# PCBproject.net
KiCad netlist of a schematic drawn in EasyEDA
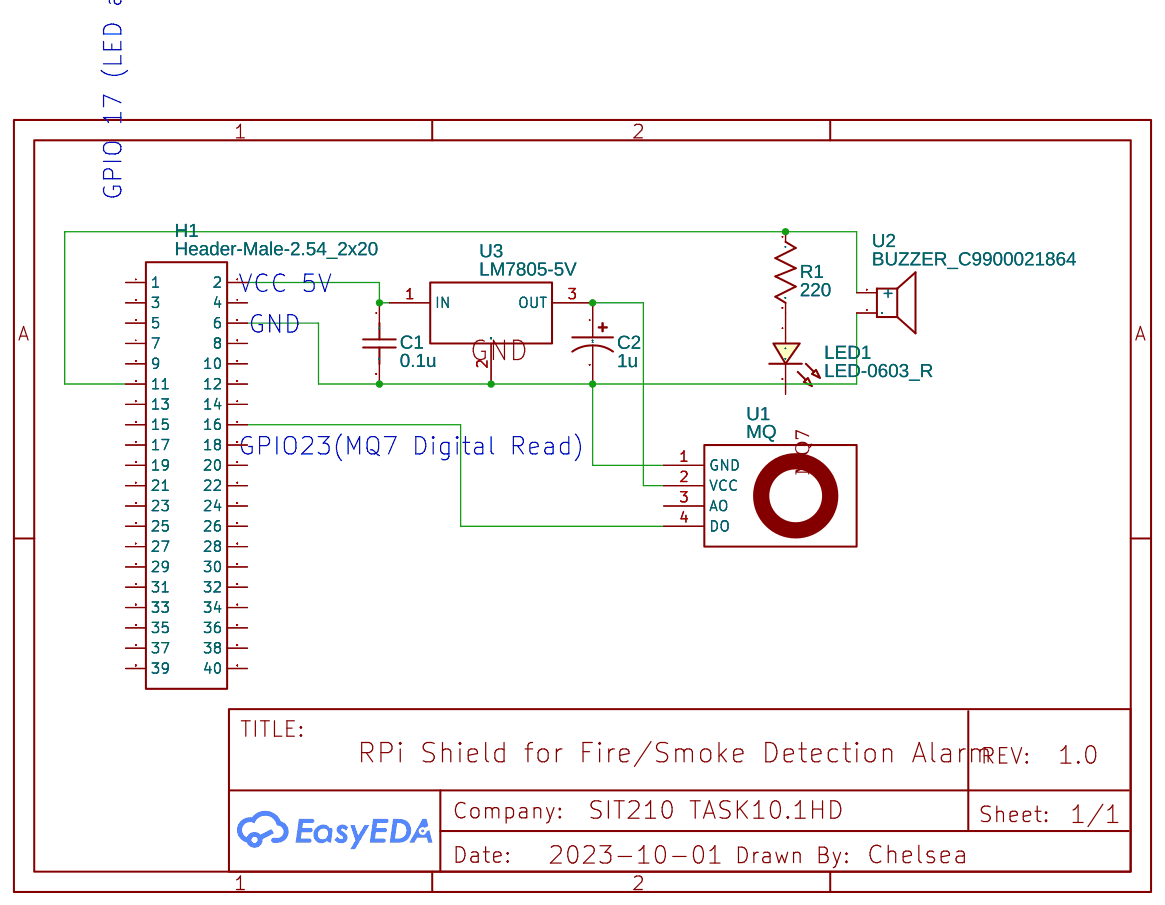
[diagram p0: schematic sheet]

(export (version "E")
  (design (tool "Eeschema 10.0.6"))
  (components
    (comp (ref "C1") (value "0.1u") (libsource (lib "") (part "C_0603_US")))
    (comp (ref "C2") (value "1u") (libsource (lib "") (part "C_Tan_SMD_A_US")))
    (comp (ref "H1")
      (value "Header-Male-2.54_2x20")
      (fields
        (field (name "Manufacturer Part") "2.54mm 2*20P直排针")
        (field (name "Manufacturer") "BOOMELE(博穆精密)")
      )
      (libsource (lib "") (part "Header-Male-2.54_2x20"))
    )
    (comp (ref "LED1")
      (value "LED-0603_R")
      (fields
        (field (name "Manufacturer Part") "19-217/R6C-AL1M2VY/3T")
        (field (name "Manufacturer") "EVERLIGHT(台湾亿光)")
      )
      (libsource (lib "") (part "LED-0603_R"))
    )
    (comp (ref "R1") (value "220") (libsource (lib "") (part "R_0603_US")))
    (comp (ref "U1") (value "MQ") (libsource (lib "") (part "MQ")))
    (comp (ref "U2")
      (value "BUZZER_C9900021864")
      (fields (field (name "Manufacturer Part") "BUZZER"))
      (libsource (lib "") (part "BUZZER_C9900021864"))
    )
    (comp (ref "U3") (value "LM7805-5V") (libsource (lib "") (part "LM7805-5V")))
  )
  (nets
    (net (code "1") (name "Net-(LED1-Pad1)") (class "Default")
      (node (ref "LED1") (pin "1") (pinfunction "1_1") (pintype "unspecified"))
      (node (ref "R1") (pin "2") (pinfunction "2_2") (pintype "unspecified"))
    )
    (net (code "2") (name "Net-(U1-DO)") (class "Default")
      (node (ref "H1") (pin "16") (pinfunction "16_16") (pintype "input"))
      (node (ref "U1") (pin "4") (pinfunction "DO_4") (pintype "unspecified"))
    )
    (net (code "3") (name "Net-(U1-GND)") (class "Default")
      (node (ref "C1") (pin "2") (pinfunction "2_2") (pintype "unspecified"))
      (node (ref "C2") (pin "2") (pinfunction "2_2") (pintype "unspecified"))
      (node (ref "H1") (pin "6") (pinfunction "6_6") (pintype "input"))
      (node (ref "U1") (pin "1") (pinfunction "GND_1") (pintype "unspecified"))
      (node (ref "U2") (pin "1") (pinfunction "1_1") (pintype "unspecified"))
      (node (ref "U3") (pin "2") (pinfunction "GND_2") (pintype "passive"))
    )
    (net (code "4") (name "Net-(U1-VCC)") (class "Default")
      (node (ref "C2") (pin "1") (pinfunction "1_1") (pintype "unspecified"))
      (node (ref "U1") (pin "2") (pinfunction "VCC_2") (pintype "unspecified"))
      (node (ref "U3") (pin "3") (pinfunction "OUT_3") (pintype "passive"))
    )
    (net (code "5") (name "Net-(U2-+)") (class "Default")
      (node (ref "H1") (pin "11") (pinfunction "11_11") (pintype "input"))
      (node (ref "R1") (pin "1") (pinfunction "1_1") (pintype "unspecified"))
      (node (ref "U2") (pin "2") (pinfunction "+_2") (pintype "unspecified"))
    )
    (net (code "6") (name "Net-(U3-IN)") (class "Default")
      (node (ref "C1") (pin "1") (pinfunction "1_1") (pintype "unspecified"))
      (node (ref "H1") (pin "2") (pinfunction "2_2") (pintype "input"))
      (node (ref "U3") (pin "1") (pinfunction "IN_1") (pintype "passive"))
    )
    (net (code "7") (name "unconnected-(H1-Pad1)") (class "Default")
      (node (ref "H1") (pin "1") (pinfunction "1_1") (pintype "input"))
    )
    (net (code "8") (name "unconnected-(H1-Pad3)") (class "Default")
      (node (ref "H1") (pin "3") (pinfunction "3_3") (pintype "input"))
    )
    (net (code "9") (name "unconnected-(H1-Pad4)") (class "Default")
      (node (ref "H1") (pin "4") (pinfunction "4_4") (pintype "input"))
    )
    (net (code "10") (name "unconnected-(H1-Pad5)") (class "Default")
      (node (ref "H1") (pin "5") (pinfunction "5_5") (pintype "input"))
    )
    (net (code "11") (name "unconnected-(H1-Pad7)") (class "Default")
      (node (ref "H1") (pin "7") (pinfunction "7_7") (pintype "input"))
    )
    (net (code "12") (name "unconnected-(H1-Pad8)") (class "Default")
      (node (ref "H1") (pin "8") (pinfunction "8_8") (pintype "input"))
    )
    (net (code "13") (name "unconnected-(H1-Pad9)") (class "Default")
      (node (ref "H1") (pin "9") (pinfunction "9_9") (pintype "input"))
    )
    (net (code "14") (name "unconnected-(H1-Pad10)") (class "Default")
      (node (ref "H1") (pin "10") (pinfunction "10_10") (pintype "input"))
    )
    (net (code "15") (name "unconnected-(H1-Pad12)") (class "Default")
      (node (ref "H1") (pin "12") (pinfunction "12_12") (pintype "input"))
    )
    (net (code "16") (name "unconnected-(H1-Pad13)") (class "Default")
      (node (ref "H1") (pin "13") (pinfunction "13_13") (pintype "input"))
    )
    (net (code "17") (name "unconnected-(H1-Pad14)") (class "Default")
      (node (ref "H1") (pin "14") (pinfunction "14_14") (pintype "input"))
    )
    (net (code "18") (name "unconnected-(H1-Pad15)") (class "Default")
      (node (ref "H1") (pin "15") (pinfunction "15_15") (pintype "input"))
    )
    (net (code "19") (name "unconnected-(H1-Pad17)") (class "Default")
      (node (ref "H1") (pin "17") (pinfunction "17_17") (pintype "input"))
    )
    (net (code "20") (name "unconnected-(H1-Pad18)") (class "Default")
      (node (ref "H1") (pin "18") (pinfunction "18_18") (pintype "input"))
    )
    (net (code "21") (name "unconnected-(H1-Pad19)") (class "Default")
      (node (ref "H1") (pin "19") (pinfunction "19_19") (pintype "input"))
    )
    (net (code "22") (name "unconnected-(H1-Pad20)") (class "Default")
      (node (ref "H1") (pin "20") (pinfunction "20_20") (pintype "input"))
    )
    (net (code "23") (name "unconnected-(H1-Pad21)") (class "Default")
      (node (ref "H1") (pin "21") (pinfunction "21_21") (pintype "input"))
    )
    (net (code "24") (name "unconnected-(H1-Pad22)") (class "Default")
      (node (ref "H1") (pin "22") (pinfunction "22_22") (pintype "input"))
    )
    (net (code "25") (name "unconnected-(H1-Pad23)") (class "Default")
      (node (ref "H1") (pin "23") (pinfunction "23_23") (pintype "input"))
    )
    (net (code "26") (name "unconnected-(H1-Pad24)") (class "Default")
      (node (ref "H1") (pin "24") (pinfunction "24_24") (pintype "input"))
    )
    (net (code "27") (name "unconnected-(H1-Pad25)") (class "Default")
      (node (ref "H1") (pin "25") (pinfunction "25_25") (pintype "input"))
    )
    (net (code "28") (name "unconnected-(H1-Pad26)") (class "Default")
      (node (ref "H1") (pin "26") (pinfunction "26_26") (pintype "input"))
    )
    (net (code "29") (name "unconnected-(H1-Pad27)") (class "Default")
      (node (ref "H1") (pin "27") (pinfunction "27_27") (pintype "input"))
    )
    (net (code "30") (name "unconnected-(H1-Pad28)") (class "Default")
      (node (ref "H1") (pin "28") (pinfunction "28_28") (pintype "input"))
    )
    (net (code "31") (name "unconnected-(H1-Pad29)") (class "Default")
      (node (ref "H1") (pin "29") (pinfunction "29_29") (pintype "input"))
    )
    (net (code "32") (name "unconnected-(H1-Pad30)") (class "Default")
      (node (ref "H1") (pin "30") (pinfunction "30_30") (pintype "input"))
    )
    (net (code "33") (name "unconnected-(H1-Pad31)") (class "Default")
      (node (ref "H1") (pin "31") (pinfunction "31_31") (pintype "input"))
    )
    (net (code "34") (name "unconnected-(H1-Pad32)") (class "Default")
      (node (ref "H1") (pin "32") (pinfunction "32_32") (pintype "input"))
    )
    (net (code "35") (name "unconnected-(H1-Pad33)") (class "Default")
      (node (ref "H1") (pin "33") (pinfunction "33_33") (pintype "input"))
    )
    (net (code "36") (name "unconnected-(H1-Pad34)") (class "Default")
      (node (ref "H1") (pin "34") (pinfunction "34_34") (pintype "input"))
    )
    (net (code "37") (name "unconnected-(H1-Pad35)") (class "Default")
      (node (ref "H1") (pin "35") (pinfunction "35_35") (pintype "input"))
    )
    (net (code "38") (name "unconnected-(H1-Pad36)") (class "Default")
      (node (ref "H1") (pin "36") (pinfunction "36_36") (pintype "input"))
    )
    (net (code "39") (name "unconnected-(H1-Pad37)") (class "Default")
      (node (ref "H1") (pin "37") (pinfunction "37_37") (pintype "input"))
    )
    (net (code "40") (name "unconnected-(H1-Pad38)") (class "Default")
      (node (ref "H1") (pin "38") (pinfunction "38_38") (pintype "input"))
    )
    (net (code "41") (name "unconnected-(H1-Pad39)") (class "Default")
      (node (ref "H1") (pin "39") (pinfunction "39_39") (pintype "input"))
    )
    (net (code "42") (name "unconnected-(H1-Pad40)") (class "Default")
      (node (ref "H1") (pin "40") (pinfunction "40_40") (pintype "input"))
    )
    (net (code "43") (name "unconnected-(LED1-Pad2)") (class "Default")
      (node (ref "LED1") (pin "2") (pinfunction "2_2") (pintype "unspecified"))
    )
    (net (code "44") (name "unconnected-(U1-AO-Pad3)") (class "Default")
      (node (ref "U1") (pin "3") (pinfunction "AO_3") (pintype "unspecified"))
    )
  )
)
